# schematic_V3.net
KiCad netlist of a schematic drawn in EAGLE
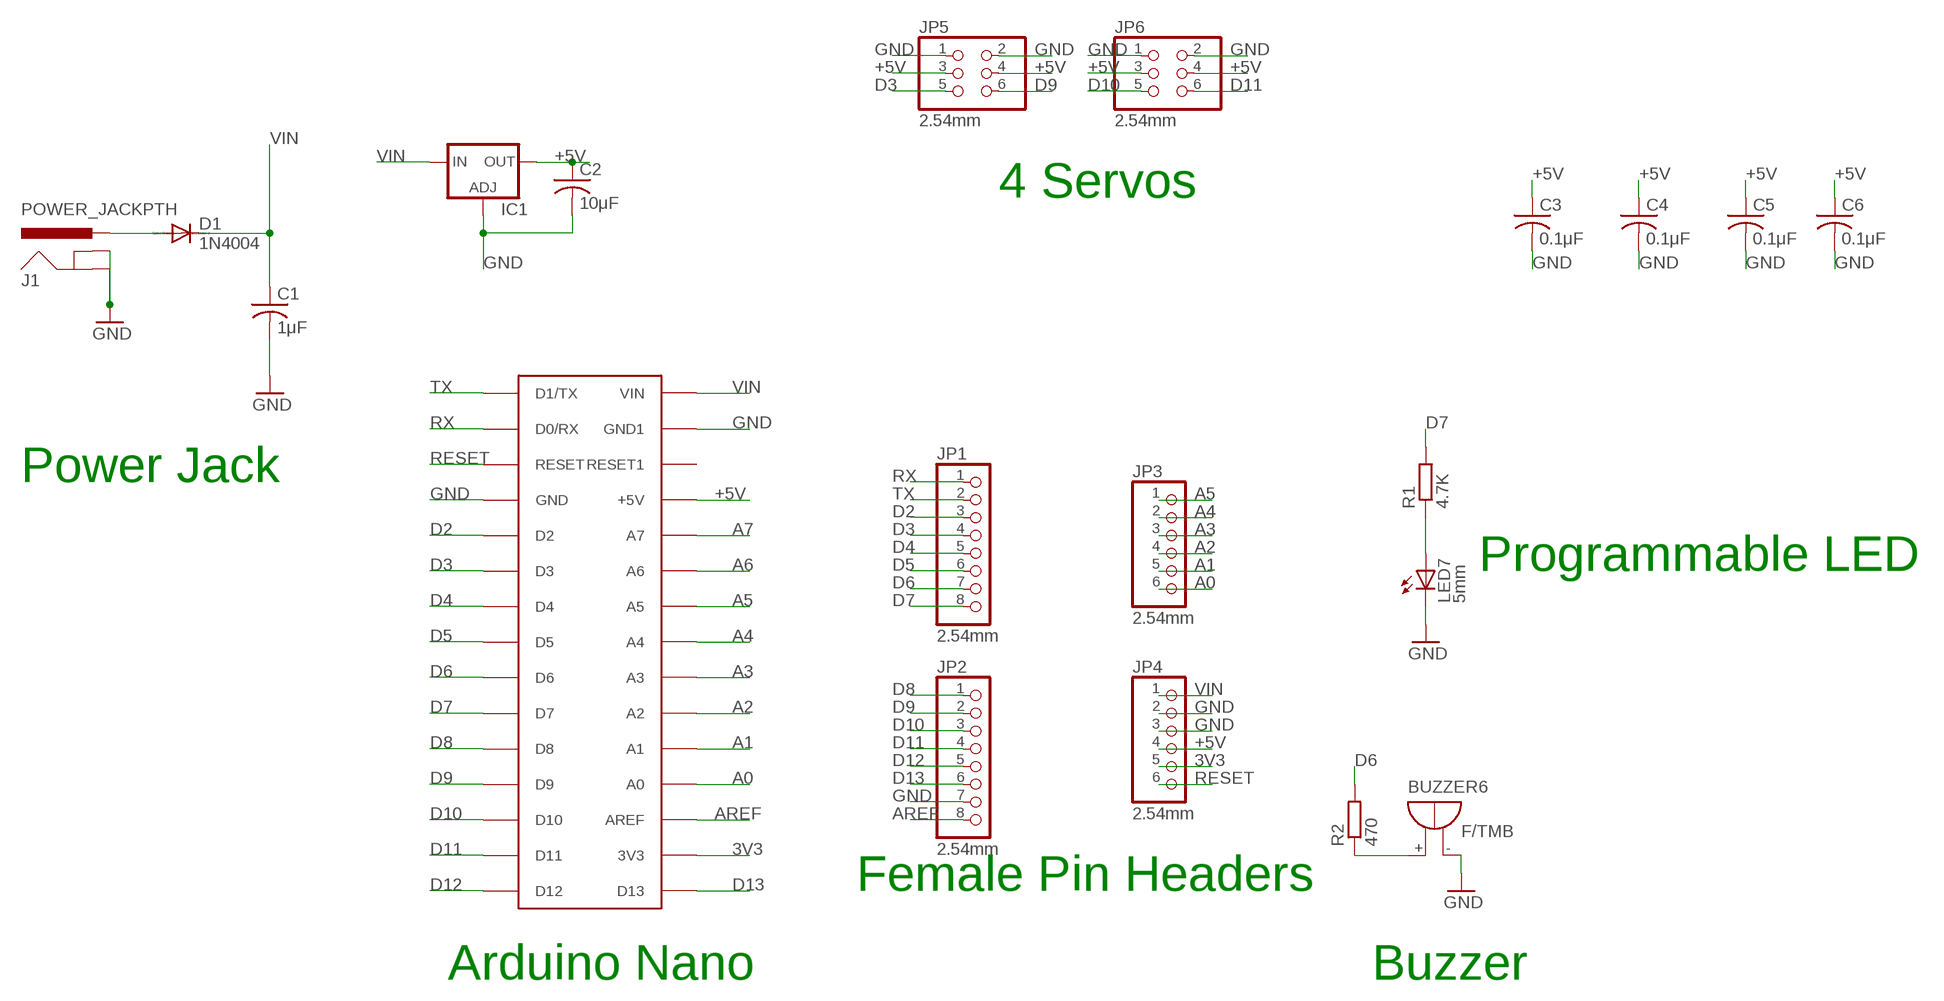
[diagram p0: schematic, sheet 1]

(export (version "E")
  (design (tool "Eeschema 10.0.6"))
  (components
    (comp (ref "BUZZER6")
      (value "F/TMB")
      (footprint "eagle-import:F_TMB")
      (libsource (lib "eagle-import") (part "F/TMB"))
    )
    (comp (ref "C1")
      (value "1μF")
      (footprint "eagle-import:C1206")
      (libsource (lib "eagle-import") (part "C-USC1206"))
    )
    (comp (ref "C2")
      (value "10μF")
      (footprint "eagle-import:C1206")
      (libsource (lib "eagle-import") (part "C-USC1206"))
    )
    (comp (ref "C3")
      (value "0.1μF")
      (footprint "eagle-import:C1206")
      (libsource (lib "eagle-import") (part "C-USC1206"))
    )
    (comp (ref "C4")
      (value "0.1μF")
      (footprint "eagle-import:C1206")
      (libsource (lib "eagle-import") (part "C-USC1206"))
    )
    (comp (ref "C5")
      (value "0.1μF")
      (footprint "eagle-import:C1206")
      (libsource (lib "eagle-import") (part "C-USC1206"))
    )
    (comp (ref "C6")
      (value "0.1μF")
      (footprint "eagle-import:C1206")
      (libsource (lib "eagle-import") (part "C-USC1206"))
    )
    (comp (ref "D1")
      (value "1N4004")
      (footprint "eagle-import:DO41-10")
      (libsource (lib "eagle-import") (part "1N4004"))
    )
    (comp (ref "IC1")
      (value "VR1")
      (footprint "eagle-import:SOT223")
      (libsource (lib "eagle-import") (part "LD117A?S33TR"))
    )
    (comp (ref "J1")
      (value "POWER_JACKPTH")
      (footprint "eagle-import:POWER_JACK_PTH")
      (libsource (lib "eagle-import") (part "POWER_JACKPTH"))
    )
    (comp (ref "JP1")
      (value "2.54mm")
      (footprint "eagle-import:1X08")
      (libsource (lib "eagle-import") (part "PINHD-1X8"))
    )
    (comp (ref "JP2")
      (value "2.54mm")
      (footprint "eagle-import:1X08")
      (libsource (lib "eagle-import") (part "PINHD-1X8"))
    )
    (comp (ref "JP3")
      (value "2.54mm")
      (footprint "eagle-import:1X06")
      (libsource (lib "eagle-import") (part "PINHD-1X6"))
    )
    (comp (ref "JP4")
      (value "2.54mm")
      (footprint "eagle-import:1X06")
      (libsource (lib "eagle-import") (part "PINHD-1X6"))
    )
    (comp (ref "JP5")
      (value "2.54mm")
      (footprint "eagle-import:2X03")
      (libsource (lib "eagle-import") (part "PINHD-2X3"))
    )
    (comp (ref "JP6")
      (value "2.54mm")
      (footprint "eagle-import:2X03")
      (libsource (lib "eagle-import") (part "PINHD-2X3"))
    )
    (comp (ref "LED7")
      (value "5mm")
      (footprint "eagle-import:LED5MM")
      (libsource (lib "eagle-import") (part "LED5MM"))
    )
    (comp (ref "R1")
      (value "4.7K")
      (footprint "eagle-import:0207_10")
      (libsource (lib "eagle-import") (part "R-EU_0207/10"))
    )
    (comp (ref "R2")
      (value "470")
      (footprint "eagle-import:0207_10")
      (libsource (lib "eagle-import") (part "R-EU_0207/10"))
    )
    (comp (ref "U$1")
      (value "ARDUINONANO")
      (footprint "eagle-import:PDIP-32")
      (libsource (lib "eagle-import") (part "ARDUINONANO"))
    )
  )
  (nets
    (net (code "1") (name "/+5V") (class "Default")
      (node (ref "C2") (pin "1") (pinfunction "1_1") (pintype "passive"))
      (node (ref "C3") (pin "1") (pinfunction "1_1") (pintype "passive"))
      (node (ref "C4") (pin "1") (pinfunction "1_1") (pintype "passive"))
      (node (ref "C5") (pin "1") (pinfunction "1_1") (pintype "passive"))
      (node (ref "C6") (pin "1") (pinfunction "1_1") (pintype "passive"))
      (node (ref "IC1") (pin "4") (pinfunction "OUT_4") (pintype "passive"))
      (node (ref "JP4") (pin "4") (pinfunction "4_4") (pintype "passive"))
      (node (ref "JP5") (pin "3") (pinfunction "3_3") (pintype "passive"))
      (node (ref "JP5") (pin "4") (pinfunction "4_4") (pintype "passive"))
      (node (ref "JP6") (pin "3") (pinfunction "3_3") (pintype "passive"))
      (node (ref "JP6") (pin "4") (pinfunction "4_4") (pintype "passive"))
      (node (ref "U$1") (pin "+5V") (pinfunction "+5V_+5V") (pintype "bidirectional"))
    )
    (net (code "2") (name "/3V3") (class "Default")
      (node (ref "JP4") (pin "5") (pinfunction "5_5") (pintype "passive"))
      (node (ref "U$1") (pin "3V3") (pinfunction "3V3_3V3") (pintype "bidirectional"))
    )
    (net (code "3") (name "/A0") (class "Default")
      (node (ref "JP3") (pin "6") (pinfunction "6_6") (pintype "passive"))
      (node (ref "U$1") (pin "A7") (pinfunction "A0_A7") (pintype "bidirectional"))
    )
    (net (code "4") (name "/A1") (class "Default")
      (node (ref "JP3") (pin "5") (pinfunction "5_5") (pintype "passive"))
      (node (ref "U$1") (pin "A6") (pinfunction "A1_A6") (pintype "bidirectional"))
    )
    (net (code "5") (name "/A2") (class "Default")
      (node (ref "JP3") (pin "4") (pinfunction "4_4") (pintype "passive"))
      (node (ref "U$1") (pin "A5") (pinfunction "A2_A5") (pintype "bidirectional"))
    )
    (net (code "6") (name "/A3") (class "Default")
      (node (ref "JP3") (pin "3") (pinfunction "3_3") (pintype "passive"))
      (node (ref "U$1") (pin "A4") (pinfunction "A3_A4") (pintype "bidirectional"))
    )
    (net (code "7") (name "/A4") (class "Default")
      (node (ref "JP3") (pin "2") (pinfunction "2_2") (pintype "passive"))
      (node (ref "U$1") (pin "A3") (pinfunction "A4_A3") (pintype "bidirectional"))
    )
    (net (code "8") (name "/A5") (class "Default")
      (node (ref "JP3") (pin "1") (pinfunction "1_1") (pintype "passive"))
      (node (ref "U$1") (pin "A2") (pinfunction "A5_A2") (pintype "bidirectional"))
    )
    (net (code "9") (name "/A6") (class "Default")
      (node (ref "U$1") (pin "A1") (pinfunction "A6_A1") (pintype "bidirectional"))
    )
    (net (code "10") (name "/A7") (class "Default")
      (node (ref "U$1") (pin "A0") (pinfunction "A7_A0") (pintype "bidirectional"))
    )
    (net (code "11") (name "/AREF") (class "Default")
      (node (ref "JP2") (pin "8") (pinfunction "8_8") (pintype "passive"))
      (node (ref "U$1") (pin "AREF") (pinfunction "AREF_AREF") (pintype "bidirectional"))
    )
    (net (code "12") (name "/D2") (class "Default")
      (node (ref "JP1") (pin "3") (pinfunction "3_3") (pintype "passive"))
      (node (ref "U$1") (pin "D2") (pinfunction "D2_D2") (pintype "bidirectional"))
    )
    (net (code "13") (name "/D3") (class "Default")
      (node (ref "JP1") (pin "4") (pinfunction "4_4") (pintype "passive"))
      (node (ref "JP5") (pin "5") (pinfunction "5_5") (pintype "passive"))
      (node (ref "U$1") (pin "D3") (pinfunction "D3_D3") (pintype "bidirectional"))
    )
    (net (code "14") (name "/D4") (class "Default")
      (node (ref "JP1") (pin "5") (pinfunction "5_5") (pintype "passive"))
      (node (ref "U$1") (pin "D4") (pinfunction "D4_D4") (pintype "bidirectional"))
    )
    (net (code "15") (name "/D5") (class "Default")
      (node (ref "JP1") (pin "6") (pinfunction "6_6") (pintype "passive"))
      (node (ref "U$1") (pin "D5") (pinfunction "D5_D5") (pintype "bidirectional"))
    )
    (net (code "16") (name "/D6") (class "Default")
      (node (ref "JP1") (pin "7") (pinfunction "7_7") (pintype "passive"))
      (node (ref "R2") (pin "2") (pinfunction "2_2") (pintype "passive"))
      (node (ref "U$1") (pin "D6") (pinfunction "D6_D6") (pintype "bidirectional"))
    )
    (net (code "17") (name "/D7") (class "Default")
      (node (ref "JP1") (pin "8") (pinfunction "8_8") (pintype "passive"))
      (node (ref "R1") (pin "2") (pinfunction "2_2") (pintype "passive"))
      (node (ref "U$1") (pin "D7") (pinfunction "D7_D7") (pintype "bidirectional"))
    )
    (net (code "18") (name "/D8") (class "Default")
      (node (ref "JP2") (pin "1") (pinfunction "1_1") (pintype "passive"))
      (node (ref "U$1") (pin "D8") (pinfunction "D8_D8") (pintype "bidirectional"))
    )
    (net (code "19") (name "/D9") (class "Default")
      (node (ref "JP2") (pin "2") (pinfunction "2_2") (pintype "passive"))
      (node (ref "JP5") (pin "6") (pinfunction "6_6") (pintype "passive"))
      (node (ref "U$1") (pin "D9") (pinfunction "D9_D9") (pintype "bidirectional"))
    )
    (net (code "20") (name "/D10") (class "Default")
      (node (ref "JP2") (pin "3") (pinfunction "3_3") (pintype "passive"))
      (node (ref "JP6") (pin "5") (pinfunction "5_5") (pintype "passive"))
      (node (ref "U$1") (pin "D10") (pinfunction "D10_D10") (pintype "bidirectional"))
    )
    (net (code "21") (name "/D11") (class "Default")
      (node (ref "JP2") (pin "4") (pinfunction "4_4") (pintype "passive"))
      (node (ref "JP6") (pin "6") (pinfunction "6_6") (pintype "passive"))
      (node (ref "U$1") (pin "D11") (pinfunction "D11_D11") (pintype "bidirectional"))
    )
    (net (code "22") (name "/D12") (class "Default")
      (node (ref "JP2") (pin "5") (pinfunction "5_5") (pintype "passive"))
      (node (ref "U$1") (pin "D12") (pinfunction "D12_D12") (pintype "bidirectional"))
    )
    (net (code "23") (name "/D13") (class "Default")
      (node (ref "JP2") (pin "6") (pinfunction "6_6") (pintype "passive"))
      (node (ref "U$1") (pin "D13") (pinfunction "D13_D13") (pintype "bidirectional"))
    )
    (net (code "24") (name "/RESET") (class "Default")
      (node (ref "JP4") (pin "6") (pinfunction "6_6") (pintype "passive"))
      (node (ref "U$1") (pin "RESET") (pinfunction "RESET_RESET") (pintype "bidirectional"))
    )
    (net (code "25") (name "/RX") (class "Default")
      (node (ref "JP1") (pin "1") (pinfunction "1_1") (pintype "passive"))
      (node (ref "U$1") (pin "D0/RX") (pinfunction "D0/RX_D0/RX") (pintype "bidirectional"))
    )
    (net (code "26") (name "/TX") (class "Default")
      (node (ref "JP1") (pin "2") (pinfunction "2_2") (pintype "passive"))
      (node (ref "U$1") (pin "D1/TX") (pinfunction "D1/TX_D1/TX") (pintype "bidirectional"))
    )
    (net (code "27") (name "/VIN") (class "Default")
      (node (ref "C1") (pin "1") (pinfunction "1_1") (pintype "passive"))
      (node (ref "D1") (pin "C") (pinfunction "C_C") (pintype "passive"))
      (node (ref "IC1") (pin "3") (pinfunction "IN_3") (pintype "input"))
      (node (ref "JP4") (pin "1") (pinfunction "1_1") (pintype "passive"))
      (node (ref "U$1") (pin "VIN") (pinfunction "VIN_VIN") (pintype "bidirectional"))
    )
    (net (code "28") (name "GND") (class "Default")
      (node (ref "BUZZER6") (pin "-") (pinfunction "-_-") (pintype "passive"))
      (node (ref "C1") (pin "2") (pinfunction "2_2") (pintype "passive"))
      (node (ref "C2") (pin "2") (pinfunction "2_2") (pintype "passive"))
      (node (ref "C3") (pin "2") (pinfunction "2_2") (pintype "passive"))
      (node (ref "C4") (pin "2") (pinfunction "2_2") (pintype "passive"))
      (node (ref "C5") (pin "2") (pinfunction "2_2") (pintype "passive"))
      (node (ref "C6") (pin "2") (pinfunction "2_2") (pintype "passive"))
      (node (ref "IC1") (pin "1") (pinfunction "ADJ_1") (pintype "input"))
      (node (ref "J1") (pin "GND") (pinfunction "GND_GND") (pintype "bidirectional"))
      (node (ref "J1") (pin "GNDBREAK") (pinfunction "GNDBREAK_GNDBREAK") (pintype "bidirectional"))
      (node (ref "JP2") (pin "7") (pinfunction "7_7") (pintype "passive"))
      (node (ref "JP4") (pin "2") (pinfunction "2_2") (pintype "passive"))
      (node (ref "JP4") (pin "3") (pinfunction "3_3") (pintype "passive"))
      (node (ref "JP5") (pin "1") (pinfunction "1_1") (pintype "passive"))
      (node (ref "JP5") (pin "2") (pinfunction "2_2") (pintype "passive"))
      (node (ref "JP6") (pin "1") (pinfunction "1_1") (pintype "passive"))
      (node (ref "JP6") (pin "2") (pinfunction "2_2") (pintype "passive"))
      (node (ref "LED7") (pin "K") (pinfunction "C_K") (pintype "passive"))
      (node (ref "U$1") (pin "GND") (pinfunction "GND_GND") (pintype "bidirectional"))
      (node (ref "U$1") (pin "GND1") (pinfunction "GND1_GND1") (pintype "bidirectional"))
    )
    (net (code "29") (name "Net-(BUZZER6-Pad+)") (class "Default")
      (node (ref "BUZZER6") (pin "+") (pinfunction "+_+") (pintype "passive"))
      (node (ref "R2") (pin "1") (pinfunction "1_1") (pintype "passive"))
    )
    (net (code "30") (name "Net-(D1-PadA)") (class "Default")
      (node (ref "D1") (pin "A") (pinfunction "A_A") (pintype "passive"))
      (node (ref "J1") (pin "PWR") (pinfunction "PWR_PWR") (pintype "bidirectional"))
    )
    (net (code "31") (name "Net-(LED7-PadA)") (class "Default")
      (node (ref "LED7") (pin "A") (pinfunction "A_A") (pintype "passive"))
      (node (ref "R1") (pin "1") (pinfunction "1_1") (pintype "passive"))
    )
    (net (code "32") (name "unconnected-(U$1-PadRESET1)") (class "Default")
      (node (ref "U$1") (pin "RESET1") (pinfunction "RESET1_RESET1") (pintype "bidirectional"))
    )
  )
)
